# Power_Distribution_-_Output_to_front_Pow.net
KiCad netlist of a schematic drawn in Altium Designer
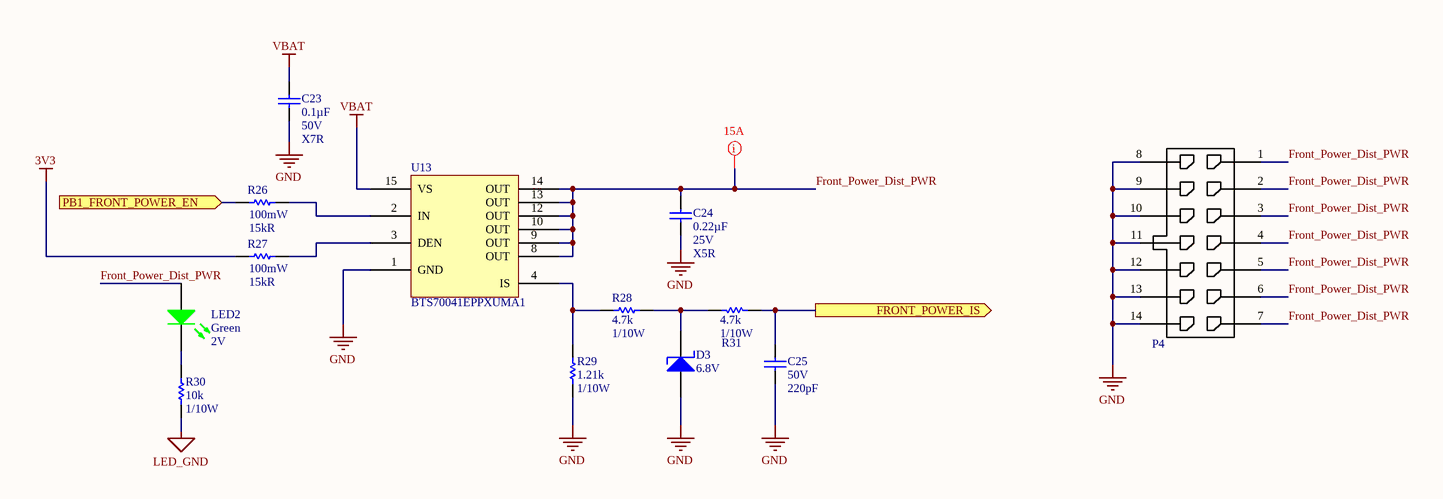
[diagram p0: Power Distribution - Output to front Power Board.SchDoc]

(export (version "E")
  (design (tool "Eeschema 10.0.6"))
  (components
    (comp (ref "C23")
      (value "CAP CER 0.1UF 50V 10% X7R 0603")
      (footprint "CAP, 0603")
      (description "0.10µF ±10% 50V Ceramic Capacitor X7R 0603 (1608 Metric)")
      (fields
        (field (name "TOLERANCE") "±10%")
        (field (name "CAPACITANCE") "0.1µF")
        (field (name "VOLTAGE") "50V")
        (field (name "TEMPERATURE COEFFICIENT") "X7R")
      )
      (libsource (lib "Schematic Diagrams") (part "CAP CER 0.1UF 50V 10% X7R 0603"))
    )
    (comp (ref "C24")
      (value "CAP CER 22uF 25V 20% X5R 0603")
      (footprint "CAP, 0603")
      (description "0.22µF ±20% 25V Ceramic Capacitor X5R 0603 (1608 Metric)")
      (fields
        (field (name "TOLERANCE") "±20%")
        (field (name "CAPACITANCE") "0.22µF")
        (field (name "VOLTAGE") "25V")
        (field (name "TEMPERATURE COEFFICIENT") "X5R")
      )
      (libsource (lib "Schematic Diagrams") (part "CAP CER 22uF 25V 20% X5R 0603"))
    )
    (comp (ref "C25")
      (value "CAP CER 220PF 50V C0G/NP0 0603")
      (footprint "CAP, 0603")
      (description "220pF ±5% 50V Ceramic Capacitor C0G, NP0 0603 (1608 Metric)")
      (fields
        (field (name "MANUFACTURER") "KEMET")
        (field (name "TOLERANCE") "5%")
        (field (name "VOLTAGE RATING") "50V")
        (field (name "CAPACITANCE") "220pF")
      )
      (libsource (lib "Schematic Diagrams") (part "CAP CER 220PF 50V C0G/NP0 0603"))
    )
    (comp (ref "D3")
      (value "6.8V")
      (footprint "DIODE SOD123")
      (description "Zener Diode 6.8V 500mW ±5% Surface Mount SOD-123")
      (fields (field (name "MANUFACTURER") "Diodes Incorporated") (field (name "TOLERANCE") "±5%"))
      (libsource (lib "Schematic Diagrams") (part "DIODE ZENER 6.8V 500MW SOD123"))
    )
    (comp (ref "LED2")
      (value "LED GREEN CLEAR 2V 0603")
      (footprint "LED_0603")
      (description "Green 572nm LED Indication - Discrete 2V 0603 (1608 Metric)")
      (fields
        (field (name "MANUFACTURER") "Wurth Electronics Inc.")
        (field (name "MANUFACTURER PART NUMBER") "150060VS75000")
        (field (name "COLOR") "Green")
        (field (name "VOLTAGE - FORWARD (VF) (TYP)") "2V")
      )
      (libsource (lib "Schematic Diagrams") (part "LED GREEN CLEAR 2V 0603"))
    )
    (comp (ref "P4")
      (value "CONN 14POS MICRO-FIT 3mm")
      (footprint "CONN, 14POS MICRO-FIT 3mm")
      (description "Connector Header Through Hole 14 position 0.118\" (3.00mm)")
      (fields
        (field (name "MANUFACTURER") "Molex, LLC")
        (field (name "MANUFACTURER PART NUMBER") "0430451427")
      )
      (libsource (lib "Schematic Diagrams") (part "CONN 14POS MICRO-FIT 3mm"))
    )
    (comp (ref "R26")
      (value "RES SMD 15K OHM 1% 1/10W 0603")
      (footprint "RES, 0603")
      (description "15 kOhms ±1% 0.1W, 1/10W Chip Resistor 0603 (1608 Metric) Moisture Resistant Thick Film")
      (fields
        (field (name "MANUFACTURER") "Yageo")
        (field (name "MANUFACTURER PART NUMBER") "RC0603FR-0715KL")
        (field (name "POWER RATING") "100mW")
        (field (name "RESISTANCE") "15kR")
      )
      (libsource (lib "Schematic Diagrams") (part "RES SMD 15K OHM 1% 1/10W 0603"))
    )
    (comp (ref "R27")
      (value "RES SMD 15K OHM 1% 1/10W 0603")
      (footprint "RES, 0603")
      (description "15 kOhms ±1% 0.1W, 1/10W Chip Resistor 0603 (1608 Metric) Moisture Resistant Thick Film")
      (fields
        (field (name "MANUFACTURER") "Yageo")
        (field (name "MANUFACTURER PART NUMBER") "RC0603FR-0715KL")
        (field (name "POWER RATING") "100mW")
        (field (name "RESISTANCE") "15kR")
      )
      (libsource (lib "Schematic Diagrams") (part "RES SMD 15K OHM 1% 1/10W 0603"))
    )
    (comp (ref "R28")
      (value "RES 4.7K OHM 1% 1/10W 0603")
      (footprint "RES, 0603")
      (description "4.7k Ohm ±1% 0.1W, 1/10W Chip Resistor 0603 (1608 Metric) Moisture Resistant Thick Film")
      (fields
        (field (name "TOLERANCE") "±1%")
        (field (name "RESISTANCE (OHMS)") "4.7k")
        (field (name "POWER (WATTS)") "1/10W")
      )
      (libsource (lib "Schematic Diagrams") (part "RES 4.7K OHM 1% 1/10W 0603"))
    )
    (comp (ref "R29")
      (value "RES 1.21K OHM 1% 1/10W 0603")
      (footprint "RES, 0603")
      (description "1.21k Ohm ±1% 0.1W, 1/10W Chip Resistor 0603 (1608 Metric) Moisture Resistant Thick Film")
      (fields
        (field (name "TOLERANCE") "±1%")
        (field (name "RESISTANCE") "1.21k")
        (field (name "POWER") "1/10W")
      )
      (libsource (lib "Schematic Diagrams") (part "RES 1.21K OHM 1% 1/10W 0603"))
    )
    (comp (ref "R30")
      (value "RES 10K OHM 1% 1/10W 0603")
      (footprint "RES, 0603")
      (description "RES SMD 10K OHM 1% 1/10W 0603")
      (fields
        (field (name "TOLERANCE") "±1%")
        (field (name "RESISTANCE") "10k")
        (field (name "POWER") "1/10W")
      )
      (libsource (lib "Schematic Diagrams") (part "RES 10K OHM 1% 1/10W 0603"))
    )
    (comp (ref "R31")
      (value "RES 4.7K OHM 1% 1/10W 0603")
      (footprint "RES, 0603")
      (description "4.7k Ohm ±1% 0.1W, 1/10W Chip Resistor 0603 (1608 Metric) Moisture Resistant Thick Film")
      (fields
        (field (name "TOLERANCE") "±1%")
        (field (name "RESISTANCE (OHMS)") "4.7k")
        (field (name "POWER (WATTS)") "1/10W")
      )
      (libsource (lib "Schematic Diagrams") (part "RES 4.7K OHM 1% 1/10W 0603"))
    )
    (comp (ref "U13")
      (value "IC LOAD SWITCH BTS70041EPPXUMA1CT-ND_1")
      (footprint "IC LOAD SWITCH PG-TSDSO-14-22")
      (description "Power Switch/Driver 1:1 N-Channel 15A PG-TSDSO-14-22")
      (fields
        (field (name "MANUFACTURER") "Infineon")
        (field (name "MANUFACTURER PART NUMBER") "BTS70041EPPXUMA1")
      )
      (libsource (lib "Schematic Diagrams") (part "IC LOAD SWITCH BTS70041EPPXUMA1CT-ND_1"))
    )
  )
  (nets
    (net (code "1") (name "/FRONT_POWER_IS") (class "Default")
      (node (ref "C25") (pin "1") (pinfunction "1_1") (pintype "passive"))
      (node (ref "R31") (pin "1") (pinfunction "1_1") (pintype "passive"))
    )
    (net (code "2") (name "/Front_Power_Dist_PWR") (class "Default")
      (node (ref "C24") (pin "1") (pinfunction "1_1") (pintype "passive"))
      (node (ref "LED2") (pin "1") (pinfunction "A_1") (pintype "passive"))
      (node (ref "P4") (pin "1") (pinfunction "1_1") (pintype "passive"))
      (node (ref "P4") (pin "2") (pinfunction "2_2") (pintype "passive"))
      (node (ref "P4") (pin "3") (pinfunction "3_3") (pintype "passive"))
      (node (ref "P4") (pin "4") (pinfunction "4_4") (pintype "passive"))
      (node (ref "P4") (pin "5") (pinfunction "5_5") (pintype "passive"))
      (node (ref "P4") (pin "6") (pinfunction "6_6") (pintype "passive"))
      (node (ref "P4") (pin "7") (pinfunction "7_7") (pintype "passive"))
      (node (ref "U13") (pin "10") (pinfunction "OUT_10") (pintype "passive"))
      (node (ref "U13") (pin "12") (pinfunction "OUT_12") (pintype "passive"))
      (node (ref "U13") (pin "13") (pinfunction "OUT_13") (pintype "passive"))
      (node (ref "U13") (pin "14") (pinfunction "OUT_14") (pintype "passive"))
      (node (ref "U13") (pin "8") (pinfunction "OUT_8") (pintype "passive"))
      (node (ref "U13") (pin "9") (pinfunction "OUT_9") (pintype "passive"))
    )
    (net (code "3") (name "/PB1_FRONT_POWER_EN") (class "Default")
      (node (ref "R26") (pin "1") (pinfunction "1_1") (pintype "passive"))
    )
    (net (code "4") (name "3V3") (class "Default")
      (node (ref "R27") (pin "1") (pinfunction "1_1") (pintype "passive"))
    )
    (net (code "5") (name "GND") (class "Default")
      (node (ref "C23") (pin "2") (pinfunction "2_2") (pintype "passive"))
      (node (ref "C24") (pin "2") (pinfunction "2_2") (pintype "passive"))
      (node (ref "C25") (pin "2") (pinfunction "2_2") (pintype "passive"))
      (node (ref "D3") (pin "2") (pinfunction "A_2") (pintype "passive"))
      (node (ref "P4") (pin "10") (pinfunction "10_10") (pintype "passive"))
      (node (ref "P4") (pin "11") (pinfunction "11_11") (pintype "passive"))
      (node (ref "P4") (pin "12") (pinfunction "12_12") (pintype "passive"))
      (node (ref "P4") (pin "13") (pinfunction "13_13") (pintype "passive"))
      (node (ref "P4") (pin "14") (pinfunction "14_14") (pintype "passive"))
      (node (ref "P4") (pin "8") (pinfunction "8_8") (pintype "passive"))
      (node (ref "P4") (pin "9") (pinfunction "9_9") (pintype "passive"))
      (node (ref "R29") (pin "2") (pinfunction "2_2") (pintype "passive"))
      (node (ref "U13") (pin "1") (pinfunction "GND_1") (pintype "passive"))
    )
    (net (code "6") (name "LED_GND") (class "Default")
      (node (ref "R30") (pin "2") (pinfunction "2_2") (pintype "passive"))
    )
    (net (code "7") (name "Net-(D3-K)") (class "Default")
      (node (ref "D3") (pin "1") (pinfunction "K_1") (pintype "passive"))
      (node (ref "R28") (pin "2") (pinfunction "2_2") (pintype "passive"))
      (node (ref "R31") (pin "2") (pinfunction "2_2") (pintype "passive"))
    )
    (net (code "8") (name "Net-(LED2-K)") (class "Default")
      (node (ref "LED2") (pin "2") (pinfunction "K_2") (pintype "passive"))
      (node (ref "R30") (pin "1") (pinfunction "1_1") (pintype "passive"))
    )
    (net (code "9") (name "Net-(U13-DEN)") (class "Default")
      (node (ref "R27") (pin "2") (pinfunction "2_2") (pintype "passive"))
      (node (ref "U13") (pin "3") (pinfunction "DEN_3") (pintype "passive"))
    )
    (net (code "10") (name "Net-(U13-IN)") (class "Default")
      (node (ref "R26") (pin "2") (pinfunction "2_2") (pintype "passive"))
      (node (ref "U13") (pin "2") (pinfunction "IN_2") (pintype "passive"))
    )
    (net (code "11") (name "Net-(U13-IS)") (class "Default")
      (node (ref "R28") (pin "1") (pinfunction "1_1") (pintype "passive"))
      (node (ref "R29") (pin "1") (pinfunction "1_1") (pintype "passive"))
      (node (ref "U13") (pin "4") (pinfunction "IS_4") (pintype "passive"))
    )
    (net (code "12") (name "VBAT") (class "Default")
      (node (ref "C23") (pin "1") (pinfunction "1_1") (pintype "passive"))
      (node (ref "U13") (pin "15") (pinfunction "VS_15") (pintype "passive"))
    )
  )
)
